# Arduino_to_LaunchPad.net
KiCad netlist of a schematic drawn in Altium Designer
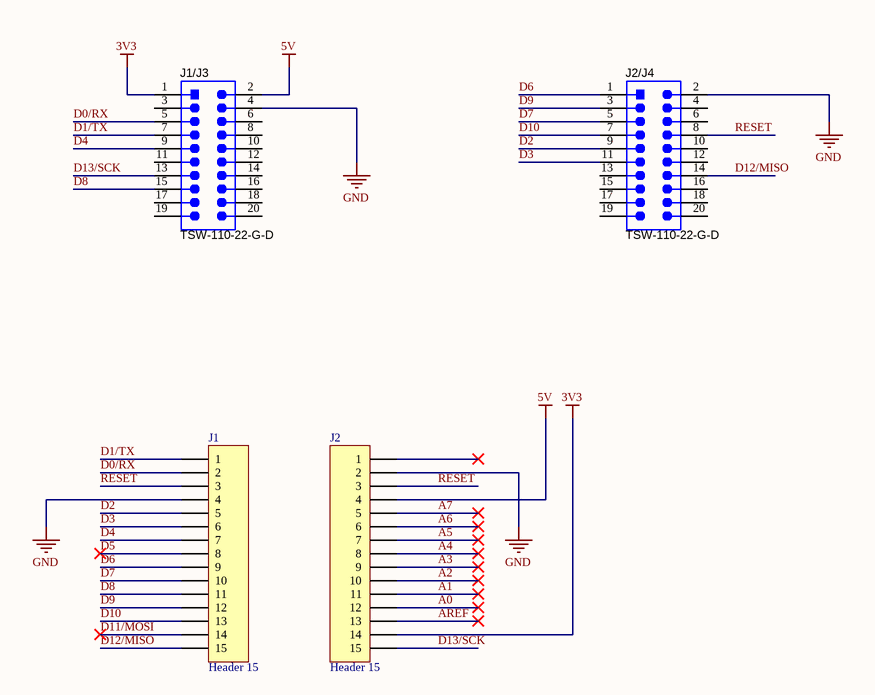
[diagram p0: Arduino_to_LaunchPad.SchDoc]

(export (version "E")
  (design (tool "Eeschema 10.0.6"))
  (components
    (comp (ref "J1")
      (value "Header 15")
      (footprint "HDR1X15")
      (description "Header, 15-Pin")
      (fields (field (name "PUBLISHER") "Altium Limited"))
      (libsource (lib "Miscellaneous Connectors") (part "Header 15"))
    )
    (comp (ref "J1/J3")
      (value "TSW-110-22-G-D")
      (footprint "Samtec_TSW-110-22-x-D")
      (description "Header, 2.54mm, 10x2, Gold, TH")
      (fields
        (field (name "MANUFACTURER") "Samtec")
        (field (name "SYMBOLCREATOR") "a0412235")
        (field (name "PUBLISHER") "Texas Instruments")
      )
      (libsource (lib "Connectors_Samtec1") (part "TSW-110-22-G-D"))
    )
    (comp (ref "J2")
      (value "Header 15")
      (footprint "HDR1X15")
      (description "Header, 15-Pin")
      (fields (field (name "PUBLISHER") "Altium Limited"))
      (libsource (lib "") (part "Header 15_1"))
    )
    (comp (ref "J2/J4")
      (value "TSW-110-22-G-D")
      (footprint "Samtec_TSW-110-22-x-D")
      (description "Header, 2.54mm, 10x2, Gold, TH")
      (fields
        (field (name "MANUFACTURER") "Samtec")
        (field (name "SYMBOLCREATOR") "a0412235")
        (field (name "PUBLISHER") "Texas Instruments")
      )
      (libsource (lib "Connectors_Samtec1") (part "TSW-110-22-G-D"))
    )
  )
  (nets
    (net (code "1") (name "/A0") (class "Default")
      (node (ref "J2") (pin "12") (pinfunction "12_12") (pintype "passive+no_connect"))
    )
    (net (code "2") (name "/A1") (class "Default")
      (node (ref "J2") (pin "11") (pinfunction "11_11") (pintype "passive+no_connect"))
    )
    (net (code "3") (name "/A2") (class "Default")
      (node (ref "J2") (pin "10") (pinfunction "10_10") (pintype "passive+no_connect"))
    )
    (net (code "4") (name "/A3") (class "Default")
      (node (ref "J2") (pin "9") (pinfunction "9_9") (pintype "passive+no_connect"))
    )
    (net (code "5") (name "/A4") (class "Default")
      (node (ref "J2") (pin "8") (pinfunction "8_8") (pintype "passive+no_connect"))
    )
    (net (code "6") (name "/A5") (class "Default")
      (node (ref "J2") (pin "7") (pinfunction "7_7") (pintype "passive+no_connect"))
    )
    (net (code "7") (name "/A6") (class "Default")
      (node (ref "J2") (pin "6") (pinfunction "6_6") (pintype "passive+no_connect"))
    )
    (net (code "8") (name "/A7") (class "Default")
      (node (ref "J2") (pin "5") (pinfunction "5_5") (pintype "passive+no_connect"))
    )
    (net (code "9") (name "/AREF") (class "Default")
      (node (ref "J2") (pin "13") (pinfunction "13_13") (pintype "passive+no_connect"))
    )
    (net (code "10") (name "/D0{slash}RX") (class "Default")
      (node (ref "J1") (pin "2") (pinfunction "2_2") (pintype "passive"))
      (node (ref "J1/J3") (pin "5") (pinfunction "5_5") (pintype "passive"))
    )
    (net (code "11") (name "/D1{slash}TX") (class "Default")
      (node (ref "J1") (pin "1") (pinfunction "1_1") (pintype "passive"))
      (node (ref "J1/J3") (pin "7") (pinfunction "7_7") (pintype "passive"))
    )
    (net (code "12") (name "/D2") (class "Default")
      (node (ref "J1") (pin "5") (pinfunction "5_5") (pintype "passive"))
      (node (ref "J2/J4") (pin "9") (pinfunction "9_9") (pintype "passive"))
    )
    (net (code "13") (name "/D3") (class "Default")
      (node (ref "J1") (pin "6") (pinfunction "6_6") (pintype "passive"))
      (node (ref "J2/J4") (pin "11") (pinfunction "11_11") (pintype "passive"))
    )
    (net (code "14") (name "/D4") (class "Default")
      (node (ref "J1") (pin "7") (pinfunction "7_7") (pintype "passive"))
      (node (ref "J1/J3") (pin "9") (pinfunction "9_9") (pintype "passive"))
    )
    (net (code "15") (name "/D5") (class "Default")
      (node (ref "J1") (pin "8") (pinfunction "8_8") (pintype "passive+no_connect"))
    )
    (net (code "16") (name "/D6") (class "Default")
      (node (ref "J1") (pin "9") (pinfunction "9_9") (pintype "passive"))
      (node (ref "J2/J4") (pin "1") (pinfunction "1_1") (pintype "passive"))
    )
    (net (code "17") (name "/D7") (class "Default")
      (node (ref "J1") (pin "10") (pinfunction "10_10") (pintype "passive"))
      (node (ref "J2/J4") (pin "5") (pinfunction "5_5") (pintype "passive"))
    )
    (net (code "18") (name "/D8") (class "Default")
      (node (ref "J1") (pin "11") (pinfunction "11_11") (pintype "passive"))
      (node (ref "J1/J3") (pin "15") (pinfunction "15_15") (pintype "passive"))
    )
    (net (code "19") (name "/D9") (class "Default")
      (node (ref "J1") (pin "12") (pinfunction "12_12") (pintype "passive"))
      (node (ref "J2/J4") (pin "3") (pinfunction "3_3") (pintype "passive"))
    )
    (net (code "20") (name "/D10") (class "Default")
      (node (ref "J1") (pin "13") (pinfunction "13_13") (pintype "passive"))
      (node (ref "J2/J4") (pin "7") (pinfunction "7_7") (pintype "passive"))
    )
    (net (code "21") (name "/D11{slash}MOSI") (class "Default")
      (node (ref "J1") (pin "14") (pinfunction "14_14") (pintype "passive+no_connect"))
    )
    (net (code "22") (name "/D12{slash}MISO") (class "Default")
      (node (ref "J1") (pin "15") (pinfunction "15_15") (pintype "passive"))
      (node (ref "J2/J4") (pin "14") (pinfunction "14_14") (pintype "passive"))
    )
    (net (code "23") (name "/D13{slash}SCK") (class "Default")
      (node (ref "J1/J3") (pin "13") (pinfunction "13_13") (pintype "passive"))
      (node (ref "J2") (pin "15") (pinfunction "15_15") (pintype "passive"))
    )
    (net (code "24") (name "/RESET") (class "Default")
      (node (ref "J1") (pin "3") (pinfunction "3_3") (pintype "passive"))
      (node (ref "J2") (pin "3") (pinfunction "3_3") (pintype "passive"))
      (node (ref "J2/J4") (pin "8") (pinfunction "8_8") (pintype "passive"))
    )
    (net (code "25") (name "3V3") (class "Default")
      (node (ref "J1/J3") (pin "1") (pinfunction "1_1") (pintype "passive"))
      (node (ref "J2") (pin "14") (pinfunction "14_14") (pintype "passive"))
    )
    (net (code "26") (name "5V") (class "Default")
      (node (ref "J1/J3") (pin "2") (pinfunction "2_2") (pintype "passive"))
      (node (ref "J2") (pin "4") (pinfunction "4_4") (pintype "passive"))
    )
    (net (code "27") (name "GND") (class "Default")
      (node (ref "J1") (pin "4") (pinfunction "4_4") (pintype "passive"))
      (node (ref "J1/J3") (pin "4") (pinfunction "4_4") (pintype "passive"))
      (node (ref "J2") (pin "2") (pinfunction "2_2") (pintype "passive"))
      (node (ref "J2/J4") (pin "2") (pinfunction "2_2") (pintype "passive"))
    )
    (net (code "28") (name "unconnected-(J1/J3-Pad3)") (class "Default")
      (node (ref "J1/J3") (pin "3") (pinfunction "3_3") (pintype "passive"))
    )
    (net (code "29") (name "unconnected-(J1/J3-Pad6)") (class "Default")
      (node (ref "J1/J3") (pin "6") (pinfunction "6_6") (pintype "passive"))
    )
    (net (code "30") (name "unconnected-(J1/J3-Pad8)") (class "Default")
      (node (ref "J1/J3") (pin "8") (pinfunction "8_8") (pintype "passive"))
    )
    (net (code "31") (name "unconnected-(J1/J3-Pad10)") (class "Default")
      (node (ref "J1/J3") (pin "10") (pinfunction "10_10") (pintype "passive"))
    )
    (net (code "32") (name "unconnected-(J1/J3-Pad11)") (class "Default")
      (node (ref "J1/J3") (pin "11") (pinfunction "11_11") (pintype "passive"))
    )
    (net (code "33") (name "unconnected-(J1/J3-Pad12)") (class "Default")
      (node (ref "J1/J3") (pin "12") (pinfunction "12_12") (pintype "passive"))
    )
    (net (code "34") (name "unconnected-(J1/J3-Pad14)") (class "Default")
      (node (ref "J1/J3") (pin "14") (pinfunction "14_14") (pintype "passive"))
    )
    (net (code "35") (name "unconnected-(J1/J3-Pad16)") (class "Default")
      (node (ref "J1/J3") (pin "16") (pinfunction "16_16") (pintype "passive"))
    )
    (net (code "36") (name "unconnected-(J1/J3-Pad17)") (class "Default")
      (node (ref "J1/J3") (pin "17") (pinfunction "17_17") (pintype "passive"))
    )
    (net (code "37") (name "unconnected-(J1/J3-Pad18)") (class "Default")
      (node (ref "J1/J3") (pin "18") (pinfunction "18_18") (pintype "passive"))
    )
    (net (code "38") (name "unconnected-(J1/J3-Pad19)") (class "Default")
      (node (ref "J1/J3") (pin "19") (pinfunction "19_19") (pintype "passive"))
    )
    (net (code "39") (name "unconnected-(J1/J3-Pad20)") (class "Default")
      (node (ref "J1/J3") (pin "20") (pinfunction "20_20") (pintype "passive"))
    )
    (net (code "40") (name "unconnected-(J2-Pad1)") (class "Default")
      (node (ref "J2") (pin "1") (pinfunction "1_1") (pintype "passive+no_connect"))
    )
    (net (code "41") (name "unconnected-(J2/J4-Pad4)") (class "Default")
      (node (ref "J2/J4") (pin "4") (pinfunction "4_4") (pintype "passive"))
    )
    (net (code "42") (name "unconnected-(J2/J4-Pad6)") (class "Default")
      (node (ref "J2/J4") (pin "6") (pinfunction "6_6") (pintype "passive"))
    )
    (net (code "43") (name "unconnected-(J2/J4-Pad10)") (class "Default")
      (node (ref "J2/J4") (pin "10") (pinfunction "10_10") (pintype "passive"))
    )
    (net (code "44") (name "unconnected-(J2/J4-Pad12)") (class "Default")
      (node (ref "J2/J4") (pin "12") (pinfunction "12_12") (pintype "passive"))
    )
    (net (code "45") (name "unconnected-(J2/J4-Pad13)") (class "Default")
      (node (ref "J2/J4") (pin "13") (pinfunction "13_13") (pintype "passive"))
    )
    (net (code "46") (name "unconnected-(J2/J4-Pad15)") (class "Default")
      (node (ref "J2/J4") (pin "15") (pinfunction "15_15") (pintype "passive"))
    )
    (net (code "47") (name "unconnected-(J2/J4-Pad16)") (class "Default")
      (node (ref "J2/J4") (pin "16") (pinfunction "16_16") (pintype "passive"))
    )
    (net (code "48") (name "unconnected-(J2/J4-Pad17)") (class "Default")
      (node (ref "J2/J4") (pin "17") (pinfunction "17_17") (pintype "passive"))
    )
    (net (code "49") (name "unconnected-(J2/J4-Pad18)") (class "Default")
      (node (ref "J2/J4") (pin "18") (pinfunction "18_18") (pintype "passive"))
    )
    (net (code "50") (name "unconnected-(J2/J4-Pad19)") (class "Default")
      (node (ref "J2/J4") (pin "19") (pinfunction "19_19") (pintype "passive"))
    )
    (net (code "51") (name "unconnected-(J2/J4-Pad20)") (class "Default")
      (node (ref "J2/J4") (pin "20") (pinfunction "20_20") (pintype "passive"))
    )
  )
)
